# crown-E.net
KiCad netlist of a schematic drawn in EAGLE
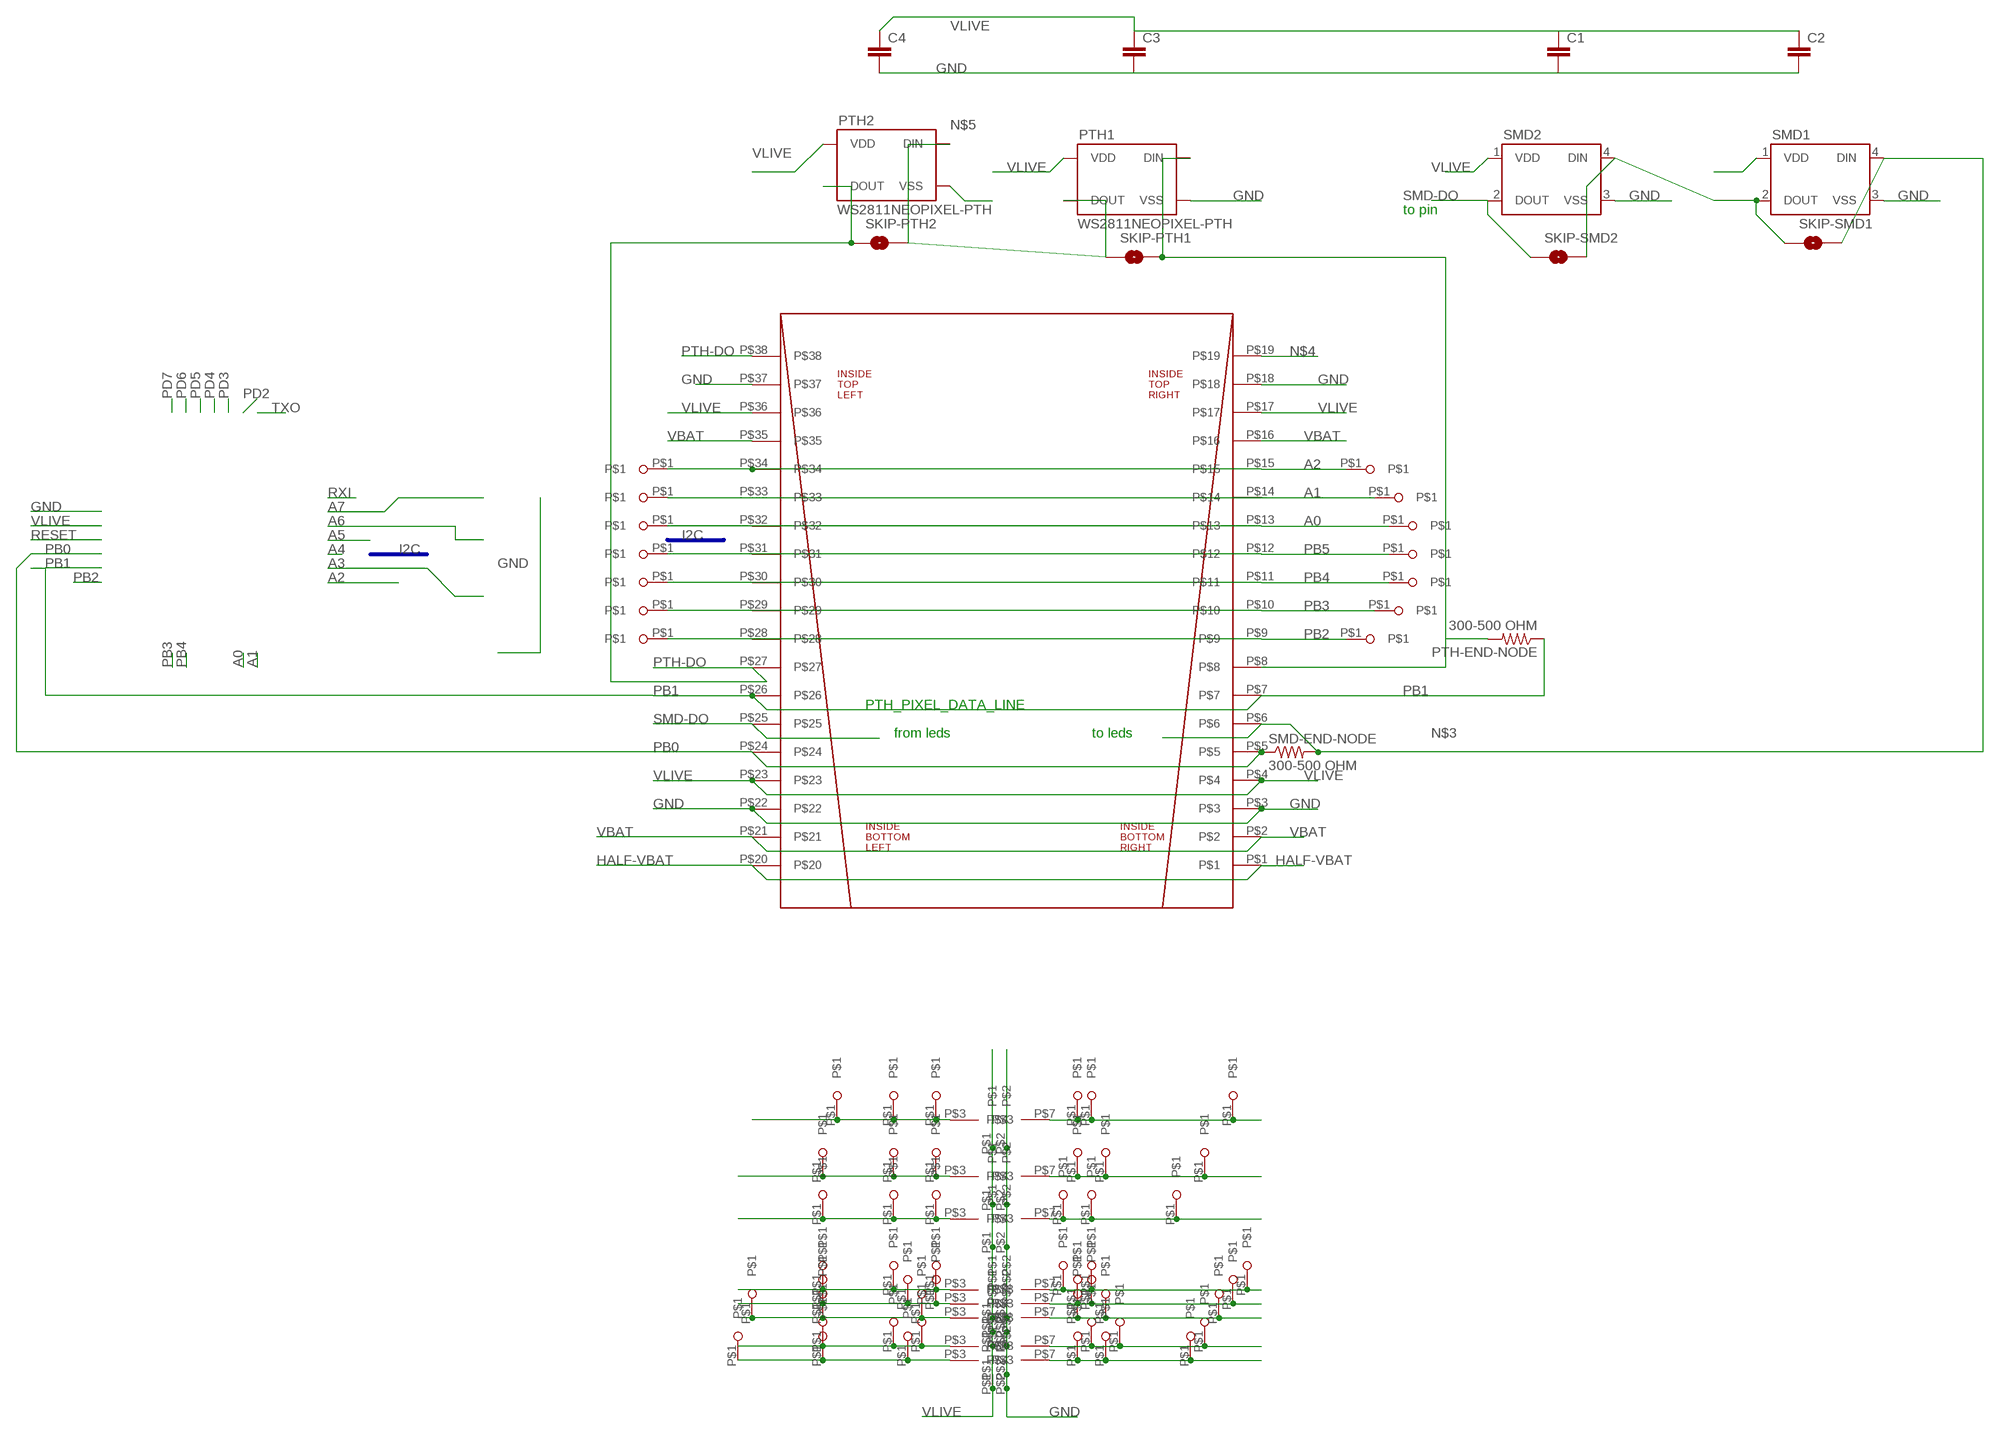
[diagram p0: schematic, sheet 1]

(export (version "E")
  (design (tool "Eeschema 10.0.6"))
  (components
    (comp (ref "C1")
      (value "CAP0805")
      (footprint "eagle-import:0805")
      (libsource (lib "eagle-import") (part "CAP0805"))
    )
    (comp (ref "C2")
      (value "CAP0805")
      (footprint "eagle-import:0805")
      (libsource (lib "eagle-import") (part "CAP0805"))
    )
    (comp (ref "C3")
      (value "CAP0805")
      (footprint "eagle-import:0805")
      (libsource (lib "eagle-import") (part "CAP0805"))
    )
    (comp (ref "C4")
      (value "CAP0805")
      (footprint "eagle-import:0805")
      (libsource (lib "eagle-import") (part "CAP0805"))
    )
    (comp (ref "PTH-END-NODE")
      (value "300-500 OHM")
      (footprint "eagle-import:0805")
      (libsource (lib "eagle-import") (part "RESISTOR0805-RES"))
    )
    (comp (ref "PTH1")
      (value "WS2811NEOPIXEL-PTH")
      (footprint "eagle-import:WS2811-PTH-FLAT")
      (libsource (lib "eagle-import") (part "WS2811NEOPIXEL-PTH"))
    )
    (comp (ref "PTH2")
      (value "WS2811NEOPIXEL-PTH")
      (footprint "eagle-import:WS2811-PTH-FLAT")
      (libsource (lib "eagle-import") (part "WS2811NEOPIXEL-PTH"))
    )
    (comp (ref "SKIP-PTH1")
      (value "SOLDERJUMPERNC2")
      (footprint "eagle-import:SJ_2S-NOTRACE")
      (libsource (lib "eagle-import") (part "SOLDERJUMPERNC2"))
    )
    (comp (ref "SKIP-PTH2")
      (value "SOLDERJUMPERNC2")
      (footprint "eagle-import:SJ_2S-NOTRACE")
      (libsource (lib "eagle-import") (part "SOLDERJUMPERNC2"))
    )
    (comp (ref "SKIP-SMD1")
      (value "SOLDERJUMPERNC2")
      (footprint "eagle-import:SJ_2S-NOTRACE")
      (libsource (lib "eagle-import") (part "SOLDERJUMPERNC2"))
    )
    (comp (ref "SKIP-SMD2")
      (value "SOLDERJUMPERNC2")
      (footprint "eagle-import:SJ_2S-NOTRACE")
      (libsource (lib "eagle-import") (part "SOLDERJUMPERNC2"))
    )
    (comp (ref "SMD-END-NODE")
      (value "300-500 OHM")
      (footprint "eagle-import:0805")
      (libsource (lib "eagle-import") (part "RESISTOR0805-RES"))
    )
    (comp (ref "SMD1")
      (value "WS2812B")
      (footprint "eagle-import:WS2812B")
      (libsource (lib "eagle-import") (part "WS2812B"))
    )
    (comp (ref "SMD2")
      (value "WS2812B")
      (footprint "eagle-import:WS2812B")
      (libsource (lib "eagle-import") (part "WS2812B"))
    )
    (comp (ref "U$1")
      (value "SMD_BREADBOARD")
      (footprint "eagle-import:SMD_BREADBOARD_4X")
      (libsource (lib "eagle-import") (part "SMD_BREADBOARD"))
    )
    (comp (ref "U$2")
      (value "CROWNSTANDARD")
      (footprint "eagle-import:CROWN")
      (libsource (lib "eagle-import") (part "CROWNSTANDARD"))
    )
    (comp (ref "U$3")
      (value "SMD_BREADBOARD")
      (footprint "eagle-import:SMD_BREADBOARD_4X")
      (libsource (lib "eagle-import") (part "SMD_BREADBOARD"))
    )
    (comp (ref "U$4")
      (value "SMD_BREADBOARD")
      (footprint "eagle-import:SMD_BREADBOARD_4X")
      (libsource (lib "eagle-import") (part "SMD_BREADBOARD"))
    )
    (comp (ref "U$5")
      (value "SMD_BREADBOARD")
      (footprint "eagle-import:SMD_BREADBOARD_4X")
      (libsource (lib "eagle-import") (part "SMD_BREADBOARD"))
    )
    (comp (ref "U$6")
      (value "SMD_BREADBOARD")
      (footprint "eagle-import:SMD_BREADBOARD_4X")
      (libsource (lib "eagle-import") (part "SMD_BREADBOARD"))
    )
    (comp (ref "U$7")
      (value "SMD_BREADBOARD")
      (footprint "eagle-import:SMD_BREADBOARD_4X")
      (libsource (lib "eagle-import") (part "SMD_BREADBOARD"))
    )
    (comp (ref "U$8")
      (value "SMD_BREADBOARD")
      (footprint "eagle-import:SMD_BREADBOARD_4X")
      (libsource (lib "eagle-import") (part "SMD_BREADBOARD"))
    )
    (comp (ref "U$9")
      (value "SMD_BREADBOARD")
      (footprint "eagle-import:SMD_BREADBOARD_4X")
      (libsource (lib "eagle-import") (part "SMD_BREADBOARD"))
    )
    (comp (ref "U$10")
      (value "SMD_PAD")
      (footprint "eagle-import:SMD_BREADBOARD_PAD")
      (libsource (lib "eagle-import") (part "SMD_PAD"))
    )
    (comp (ref "U$11")
      (value "SMD_PAD")
      (footprint "eagle-import:SMD_BREADBOARD_PAD")
      (libsource (lib "eagle-import") (part "SMD_PAD"))
    )
    (comp (ref "U$12")
      (value "SMD_PAD")
      (footprint "eagle-import:SMD_BREADBOARD_PAD")
      (libsource (lib "eagle-import") (part "SMD_PAD"))
    )
    (comp (ref "U$13")
      (value "SMD_PAD")
      (footprint "eagle-import:SMD_BREADBOARD_PAD")
      (libsource (lib "eagle-import") (part "SMD_PAD"))
    )
    (comp (ref "U$14")
      (value "SMD_PAD")
      (footprint "eagle-import:SMD_BREADBOARD_PAD")
      (libsource (lib "eagle-import") (part "SMD_PAD"))
    )
    (comp (ref "U$15")
      (value "SMD_PAD")
      (footprint "eagle-import:SMD_BREADBOARD_PAD")
      (libsource (lib "eagle-import") (part "SMD_PAD"))
    )
    (comp (ref "U$16")
      (value "SMD_PAD")
      (footprint "eagle-import:SMD_BREADBOARD_PAD")
      (libsource (lib "eagle-import") (part "SMD_PAD"))
    )
    (comp (ref "U$17")
      (value "SMD_PAD")
      (footprint "eagle-import:SMD_BREADBOARD_PAD")
      (libsource (lib "eagle-import") (part "SMD_PAD"))
    )
    (comp (ref "U$18")
      (value "SMD_PAD")
      (footprint "eagle-import:SMD_BREADBOARD_PAD")
      (libsource (lib "eagle-import") (part "SMD_PAD"))
    )
    (comp (ref "U$19")
      (value "SMD_PAD")
      (footprint "eagle-import:SMD_BREADBOARD_PAD")
      (libsource (lib "eagle-import") (part "SMD_PAD"))
    )
    (comp (ref "U$20")
      (value "SMD_PAD")
      (footprint "eagle-import:SMD_BREADBOARD_PAD")
      (libsource (lib "eagle-import") (part "SMD_PAD"))
    )
    (comp (ref "U$21")
      (value "SMD_PAD")
      (footprint "eagle-import:SMD_BREADBOARD_PAD")
      (libsource (lib "eagle-import") (part "SMD_PAD"))
    )
    (comp (ref "U$22")
      (value "SMD_PAD")
      (footprint "eagle-import:SMD_BREADBOARD_PAD")
      (libsource (lib "eagle-import") (part "SMD_PAD"))
    )
    (comp (ref "U$23")
      (value "SMD_PAD")
      (footprint "eagle-import:SMD_BREADBOARD_PAD")
      (libsource (lib "eagle-import") (part "SMD_PAD"))
    )
    (comp (ref "U$24")
      (value "SMD_PAD")
      (footprint "eagle-import:SMD_BREADBOARD_PAD")
      (libsource (lib "eagle-import") (part "SMD_PAD"))
    )
    (comp (ref "U$25")
      (value "SMD_PAD")
      (footprint "eagle-import:SMD_BREADBOARD_PAD")
      (libsource (lib "eagle-import") (part "SMD_PAD"))
    )
    (comp (ref "U$26")
      (value "SMD_PAD")
      (footprint "eagle-import:SMD_BREADBOARD_PAD")
      (libsource (lib "eagle-import") (part "SMD_PAD"))
    )
    (comp (ref "U$27")
      (value "SMD_PAD")
      (footprint "eagle-import:SMD_BREADBOARD_PAD")
      (libsource (lib "eagle-import") (part "SMD_PAD"))
    )
    (comp (ref "U$28")
      (value "SMD_PAD")
      (footprint "eagle-import:SMD_BREADBOARD_PAD")
      (libsource (lib "eagle-import") (part "SMD_PAD"))
    )
    (comp (ref "U$29")
      (value "SMD_PAD")
      (footprint "eagle-import:SMD_BREADBOARD_PAD")
      (libsource (lib "eagle-import") (part "SMD_PAD"))
    )
    (comp (ref "U$30")
      (value "SMD_PAD")
      (footprint "eagle-import:SMD_BREADBOARD_PAD")
      (libsource (lib "eagle-import") (part "SMD_PAD"))
    )
    (comp (ref "U$31")
      (value "SMD_PAD")
      (footprint "eagle-import:SMD_BREADBOARD_PAD")
      (libsource (lib "eagle-import") (part "SMD_PAD"))
    )
    (comp (ref "U$32")
      (value "SMD_PAD")
      (footprint "eagle-import:SMD_BREADBOARD_PAD")
      (libsource (lib "eagle-import") (part "SMD_PAD"))
    )
    (comp (ref "U$33")
      (value "SMD_PAD")
      (footprint "eagle-import:SMD_BREADBOARD_PAD")
      (libsource (lib "eagle-import") (part "SMD_PAD"))
    )
    (comp (ref "U$34")
      (value "SMD_PAD")
      (footprint "eagle-import:SMD_BREADBOARD_PAD")
      (libsource (lib "eagle-import") (part "SMD_PAD"))
    )
    (comp (ref "U$35")
      (value "SMD_PAD")
      (footprint "eagle-import:SMD_BREADBOARD_PAD")
      (libsource (lib "eagle-import") (part "SMD_PAD"))
    )
    (comp (ref "U$36")
      (value "SMD_PAD")
      (footprint "eagle-import:SMD_BREADBOARD_PAD")
      (libsource (lib "eagle-import") (part "SMD_PAD"))
    )
    (comp (ref "U$37")
      (value "SMD_PAD")
      (footprint "eagle-import:SMD_BREADBOARD_PAD")
      (libsource (lib "eagle-import") (part "SMD_PAD"))
    )
    (comp (ref "U$38")
      (value "SMD_PAD")
      (footprint "eagle-import:SMD_BREADBOARD_PAD")
      (libsource (lib "eagle-import") (part "SMD_PAD"))
    )
    (comp (ref "U$39")
      (value "SMD_PAD")
      (footprint "eagle-import:SMD_BREADBOARD_PAD")
      (libsource (lib "eagle-import") (part "SMD_PAD"))
    )
    (comp (ref "U$40")
      (value "SMD_PAD")
      (footprint "eagle-import:SMD_BREADBOARD_PAD")
      (libsource (lib "eagle-import") (part "SMD_PAD"))
    )
    (comp (ref "U$41")
      (value "SMD_PAD")
      (footprint "eagle-import:SMD_BREADBOARD_PAD")
      (libsource (lib "eagle-import") (part "SMD_PAD"))
    )
    (comp (ref "U$42")
      (value "SMD_PAD")
      (footprint "eagle-import:SMD_BREADBOARD_PAD")
      (libsource (lib "eagle-import") (part "SMD_PAD"))
    )
    (comp (ref "U$43")
      (value "SMD_PAD")
      (footprint "eagle-import:SMD_BREADBOARD_PAD")
      (libsource (lib "eagle-import") (part "SMD_PAD"))
    )
    (comp (ref "U$44")
      (value "SMD_PAD")
      (footprint "eagle-import:SMD_BREADBOARD_PAD")
      (libsource (lib "eagle-import") (part "SMD_PAD"))
    )
    (comp (ref "U$45")
      (value "SMD_PAD")
      (footprint "eagle-import:SMD_BREADBOARD_PAD")
      (libsource (lib "eagle-import") (part "SMD_PAD"))
    )
    (comp (ref "U$46")
      (value "SMD_PAD")
      (footprint "eagle-import:SMD_BREADBOARD_PAD")
      (libsource (lib "eagle-import") (part "SMD_PAD"))
    )
    (comp (ref "U$47")
      (value "SMD_PAD")
      (footprint "eagle-import:SMD_BREADBOARD_PAD")
      (libsource (lib "eagle-import") (part "SMD_PAD"))
    )
    (comp (ref "U$48")
      (value "SMD_PAD")
      (footprint "eagle-import:SMD_BREADBOARD_PAD")
      (libsource (lib "eagle-import") (part "SMD_PAD"))
    )
    (comp (ref "U$49")
      (value "SMD_PAD")
      (footprint "eagle-import:SMD_BREADBOARD_PAD")
      (libsource (lib "eagle-import") (part "SMD_PAD"))
    )
    (comp (ref "U$50")
      (value "SMD_PAD")
      (footprint "eagle-import:SMD_BREADBOARD_PAD")
      (libsource (lib "eagle-import") (part "SMD_PAD"))
    )
    (comp (ref "U$51")
      (value "SMD_PAD")
      (footprint "eagle-import:SMD_BREADBOARD_PAD")
      (libsource (lib "eagle-import") (part "SMD_PAD"))
    )
    (comp (ref "U$52")
      (value "SMD_PAD")
      (footprint "eagle-import:SMD_BREADBOARD_PAD")
      (libsource (lib "eagle-import") (part "SMD_PAD"))
    )
    (comp (ref "U$53")
      (value "SMD_PAD")
      (footprint "eagle-import:SMD_BREADBOARD_PAD")
      (libsource (lib "eagle-import") (part "SMD_PAD"))
    )
    (comp (ref "U$54")
      (value "SMD_PAD")
      (footprint "eagle-import:SMD_BREADBOARD_PAD")
      (libsource (lib "eagle-import") (part "SMD_PAD"))
    )
    (comp (ref "U$55")
      (value "SMD_PAD")
      (footprint "eagle-import:SMD_BREADBOARD_PAD")
      (libsource (lib "eagle-import") (part "SMD_PAD"))
    )
    (comp (ref "U$56")
      (value "SMD_PAD")
      (footprint "eagle-import:SMD_BREADBOARD_PAD")
      (libsource (lib "eagle-import") (part "SMD_PAD"))
    )
    (comp (ref "U$57")
      (value "SMD_PAD")
      (footprint "eagle-import:SMD_BREADBOARD_PAD")
      (libsource (lib "eagle-import") (part "SMD_PAD"))
    )
    (comp (ref "U$58")
      (value "SMD_PAD")
      (footprint "eagle-import:SMD_BREADBOARD_PAD")
      (libsource (lib "eagle-import") (part "SMD_PAD"))
    )
    (comp (ref "U$59")
      (value "SMD_PAD")
      (footprint "eagle-import:SMD_BREADBOARD_PAD")
      (libsource (lib "eagle-import") (part "SMD_PAD"))
    )
    (comp (ref "U$60")
      (value "SMD_PAD")
      (footprint "eagle-import:SMD_BREADBOARD_PAD")
      (libsource (lib "eagle-import") (part "SMD_PAD"))
    )
    (comp (ref "U$61")
      (value "SMD_PAD")
      (footprint "eagle-import:SMD_BREADBOARD_PAD")
      (libsource (lib "eagle-import") (part "SMD_PAD"))
    )
    (comp (ref "U$62")
      (value "SMD_PAD")
      (footprint "eagle-import:SMD_BREADBOARD_PAD")
      (libsource (lib "eagle-import") (part "SMD_PAD"))
    )
    (comp (ref "U$63")
      (value "SMD_PAD")
      (footprint "eagle-import:SMD_BREADBOARD_PAD")
      (libsource (lib "eagle-import") (part "SMD_PAD"))
    )
    (comp (ref "U$64")
      (value "SMD_PAD")
      (footprint "eagle-import:SMD_BREADBOARD_PAD")
      (libsource (lib "eagle-import") (part "SMD_PAD"))
    )
    (comp (ref "U$65")
      (value "SMD_PAD")
      (footprint "eagle-import:SMD_BREADBOARD_PAD")
      (libsource (lib "eagle-import") (part "SMD_PAD"))
    )
    (comp (ref "U$66")
      (value "SMD_PAD")
      (footprint "eagle-import:SMD_BREADBOARD_PAD")
      (libsource (lib "eagle-import") (part "SMD_PAD"))
    )
    (comp (ref "U$67")
      (value "SMD_PAD")
      (footprint "eagle-import:SMD_BREADBOARD_PAD")
      (libsource (lib "eagle-import") (part "SMD_PAD"))
    )
    (comp (ref "U$68")
      (value "SMD_PAD")
      (footprint "eagle-import:SMD_BREADBOARD_PAD")
      (libsource (lib "eagle-import") (part "SMD_PAD"))
    )
    (comp (ref "U$69")
      (value "SMD_PAD")
      (footprint "eagle-import:SMD_BREADBOARD_PAD")
      (libsource (lib "eagle-import") (part "SMD_PAD"))
    )
    (comp (ref "U$70")
      (value "SMD_PAD")
      (footprint "eagle-import:SMD_BREADBOARD_PAD")
      (libsource (lib "eagle-import") (part "SMD_PAD"))
    )
    (comp (ref "U$71")
      (value "SMD_PAD")
      (footprint "eagle-import:SMD_BREADBOARD_PAD")
      (libsource (lib "eagle-import") (part "SMD_PAD"))
    )
  )
  (nets
    (net (code "2") (name "/A0") (class "Default")
      (node (ref "U$2") (pin "P$13") (pinfunction "P$13_P$13") (pintype "bidirectional"))
      (node (ref "U$2") (pin "P$32") (pinfunction "P$32_P$32") (pintype "bidirectional"))
      (node (ref "U$44") (pin "P$1") (pinfunction "P$1_P$1") (pintype "bidirectional"))
      (node (ref "U$55") (pin "P$1") (pinfunction "P$1_P$1") (pintype "bidirectional"))
    )
    (net (code "3") (name "/A1") (class "Default")
      (node (ref "U$2") (pin "P$14") (pinfunction "P$14_P$14") (pintype "bidirectional"))
      (node (ref "U$2") (pin "P$33") (pinfunction "P$33_P$33") (pintype "bidirectional"))
      (node (ref "U$43") (pin "P$1") (pinfunction "P$1_P$1") (pintype "bidirectional"))
      (node (ref "U$56") (pin "P$1") (pinfunction "P$1_P$1") (pintype "bidirectional"))
    )
    (net (code "4") (name "/A2") (class "Default")
      (node (ref "U$2") (pin "P$15") (pinfunction "P$15_P$15") (pintype "bidirectional"))
      (node (ref "U$2") (pin "P$34") (pinfunction "P$34_P$34") (pintype "bidirectional"))
      (node (ref "U$42") (pin "P$1") (pinfunction "P$1_P$1") (pintype "bidirectional"))
      (node (ref "U$58") (pin "P$1") (pinfunction "P$1_P$1") (pintype "bidirectional"))
    )
    (net (code "10") (name "/GND") (class "Default")
      (node (ref "C1") (pin "2") (pinfunction "2_2") (pintype "passive"))
      (node (ref "C2") (pin "2") (pinfunction "2_2") (pintype "passive"))
      (node (ref "C3") (pin "2") (pinfunction "2_2") (pintype "passive"))
      (node (ref "C4") (pin "2") (pinfunction "2_2") (pintype "passive"))
      (node (ref "PTH1") (pin "P$2") (pinfunction "VSS_P$2") (pintype "power_in"))
      (node (ref "PTH1") (pin "P$6") (pinfunction "VSS_P$6") (pintype "power_in"))
      (node (ref "PTH2") (pin "P$2") (pinfunction "VSS_P$2") (pintype "power_in"))
      (node (ref "PTH2") (pin "P$6") (pinfunction "VSS_P$6") (pintype "power_in"))
      (node (ref "SMD1") (pin "3") (pinfunction "VSS_3") (pintype "power_in"))
      (node (ref "SMD2") (pin "3") (pinfunction "VSS_3") (pintype "power_in"))
      (node (ref "U$1") (pin "P$2") (pinfunction "P$2_P$2") (pintype "bidirectional"))
      (node (ref "U$2") (pin "P$18") (pinfunction "P$18_P$18") (pintype "bidirectional"))
      (node (ref "U$2") (pin "P$22") (pinfunction "P$22_P$22") (pintype "bidirectional"))
      (node (ref "U$2") (pin "P$3") (pinfunction "P$3_P$3") (pintype "bidirectional"))
      (node (ref "U$2") (pin "P$37") (pinfunction "P$37_P$37") (pintype "bidirectional"))
      (node (ref "U$3") (pin "P$2") (pinfunction "P$2_P$2") (pintype "bidirectional"))
      (node (ref "U$4") (pin "P$2") (pinfunction "P$2_P$2") (pintype "bidirectional"))
      (node (ref "U$5") (pin "P$2") (pinfunction "P$2_P$2") (pintype "bidirectional"))
      (node (ref "U$6") (pin "P$2") (pinfunction "P$2_P$2") (pintype "bidirectional"))
      (node (ref "U$7") (pin "P$2") (pinfunction "P$2_P$2") (pintype "bidirectional"))
      (node (ref "U$8") (pin "P$2") (pinfunction "P$2_P$2") (pintype "bidirectional"))
      (node (ref "U$9") (pin "P$2") (pinfunction "P$2_P$2") (pintype "bidirectional"))
    )
    (net (code "11") (name "/HALF-VBAT") (class "Default")
      (node (ref "U$2") (pin "P$1") (pinfunction "P$1_P$1") (pintype "bidirectional"))
      (node (ref "U$2") (pin "P$20") (pinfunction "P$20_P$20") (pintype "bidirectional"))
    )
    (net (code "12") (name "/N$3") (class "Default")
      (node (ref "SKIP-SMD1") (pin "2") (pinfunction "2_2") (pintype "passive"))
      (node (ref "SMD-END-NODE") (pin "2") (pinfunction "2_2") (pintype "passive"))
      (node (ref "SMD1") (pin "4") (pinfunction "DIN_4") (pintype "input"))
      (node (ref "U$2") (pin "P$6") (pinfunction "P$6_P$6") (pintype "bidirectional"))
    )
    (net (code "13") (name "/N$4") (class "Default")
      (node (ref "PTH-END-NODE") (pin "2") (pinfunction "2_2") (pintype "passive"))
      (node (ref "PTH1") (pin "P$4") (pinfunction "DIN_P$4") (pintype "input"))
      (node (ref "PTH1") (pin "P$8") (pinfunction "DIN_P$8") (pintype "input"))
      (node (ref "SKIP-PTH1") (pin "2") (pinfunction "2_2") (pintype "passive"))
      (node (ref "U$2") (pin "P$19") (pinfunction "P$19_P$19") (pintype "bidirectional"))
      (node (ref "U$2") (pin "P$8") (pinfunction "P$8_P$8") (pintype "bidirectional"))
    )
    (net (code "14") (name "/N$5") (class "Default")
      (node (ref "PTH1") (pin "P$1") (pinfunction "DOUT_P$1") (pintype "output"))
      (node (ref "PTH1") (pin "P$5") (pinfunction "DOUT_P$5") (pintype "output"))
      (node (ref "PTH2") (pin "P$4") (pinfunction "DIN_P$4") (pintype "input"))
      (node (ref "PTH2") (pin "P$8") (pinfunction "DIN_P$8") (pintype "input"))
      (node (ref "SKIP-PTH1") (pin "1") (pinfunction "1_1") (pintype "passive"))
      (node (ref "SKIP-PTH2") (pin "2") (pinfunction "2_2") (pintype "passive"))
    )
    (net (code "15") (name "/PB0") (class "Default")
      (node (ref "SMD-END-NODE") (pin "1") (pinfunction "1_1") (pintype "passive"))
      (node (ref "U$2") (pin "P$24") (pinfunction "P$24_P$24") (pintype "bidirectional"))
      (node (ref "U$2") (pin "P$5") (pinfunction "P$5_P$5") (pintype "bidirectional"))
    )
    (net (code "16") (name "/PB1") (class "Default")
      (node (ref "PTH-END-NODE") (pin "1") (pinfunction "1_1") (pintype "passive"))
      (node (ref "U$2") (pin "P$26") (pinfunction "P$26_P$26") (pintype "bidirectional"))
      (node (ref "U$2") (pin "P$7") (pinfunction "P$7_P$7") (pintype "bidirectional"))
    )
    (net (code "17") (name "/PB2") (class "Default")
      (node (ref "U$2") (pin "P$28") (pinfunction "P$28_P$28") (pintype "bidirectional"))
      (node (ref "U$2") (pin "P$9") (pinfunction "P$9_P$9") (pintype "bidirectional"))
      (node (ref "U$48") (pin "P$1") (pinfunction "P$1_P$1") (pintype "bidirectional"))
      (node (ref "U$51") (pin "P$1") (pinfunction "P$1_P$1") (pintype "bidirectional"))
    )
    (net (code "18") (name "/PB3") (class "Default")
      (node (ref "U$2") (pin "P$10") (pinfunction "P$10_P$10") (pintype "bidirectional"))
      (node (ref "U$2") (pin "P$29") (pinfunction "P$29_P$29") (pintype "bidirectional"))
      (node (ref "U$47") (pin "P$1") (pinfunction "P$1_P$1") (pintype "bidirectional"))
      (node (ref "U$52") (pin "P$1") (pinfunction "P$1_P$1") (pintype "bidirectional"))
    )
    (net (code "19") (name "/PB4") (class "Default")
      (node (ref "U$2") (pin "P$11") (pinfunction "P$11_P$11") (pintype "bidirectional"))
      (node (ref "U$2") (pin "P$30") (pinfunction "P$30_P$30") (pintype "bidirectional"))
      (node (ref "U$46") (pin "P$1") (pinfunction "P$1_P$1") (pintype "bidirectional"))
      (node (ref "U$53") (pin "P$1") (pinfunction "P$1_P$1") (pintype "bidirectional"))
    )
    (net (code "20") (name "/PB5") (class "Default")
      (node (ref "U$2") (pin "P$12") (pinfunction "P$12_P$12") (pintype "bidirectional"))
      (node (ref "U$2") (pin "P$31") (pinfunction "P$31_P$31") (pintype "bidirectional"))
      (node (ref "U$45") (pin "P$1") (pinfunction "P$1_P$1") (pintype "bidirectional"))
      (node (ref "U$54") (pin "P$1") (pinfunction "P$1_P$1") (pintype "bidirectional"))
    )
    (net (code "27") (name "/PTH-DO") (class "Default")
      (node (ref "PTH2") (pin "P$1") (pinfunction "DOUT_P$1") (pintype "output"))
      (node (ref "PTH2") (pin "P$5") (pinfunction "DOUT_P$5") (pintype "output"))
      (node (ref "SKIP-PTH2") (pin "1") (pinfunction "1_1") (pintype "passive"))
      (node (ref "U$2") (pin "P$27") (pinfunction "P$27_P$27") (pintype "bidirectional"))
      (node (ref "U$2") (pin "P$38") (pinfunction "P$38_P$38") (pintype "bidirectional"))
    )
    (net (code "30") (name "/SMD-DO") (class "Default")
      (node (ref "SKIP-SMD2") (pin "1") (pinfunction "1_1") (pintype "passive"))
      (node (ref "SMD2") (pin "2") (pinfunction "DOUT_2") (pintype "output"))
      (node (ref "U$2") (pin "P$25") (pinfunction "P$25_P$25") (pintype "bidirectional"))
    )
    (net (code "32") (name "/VBAT") (class "Default")
      (node (ref "U$2") (pin "P$16") (pinfunction "P$16_P$16") (pintype "bidirectional"))
      (node (ref "U$2") (pin "P$2") (pinfunction "P$2_P$2") (pintype "bidirectional"))
      (node (ref "U$2") (pin "P$21") (pinfunction "P$21_P$21") (pintype "bidirectional"))
      (node (ref "U$2") (pin "P$35") (pinfunction "P$35_P$35") (pintype "bidirectional"))
    )
    (net (code "33") (name "/VLIVE") (class "Default")
      (node (ref "C1") (pin "1") (pinfunction "1_1") (pintype "passive"))
      (node (ref "C2") (pin "1") (pinfunction "1_1") (pintype "passive"))
      (node (ref "C3") (pin "1") (pinfunction "1_1") (pintype "passive"))
      (node (ref "C4") (pin "1") (pinfunction "1_1") (pintype "passive"))
      (node (ref "PTH1") (pin "P$3") (pinfunction "VDD_P$3") (pintype "power_in"))
      (node (ref "PTH1") (pin "P$7") (pinfunction "VDD_P$7") (pintype "power_in"))
      (node (ref "PTH2") (pin "P$3") (pinfunction "VDD_P$3") (pintype "power_in"))
      (node (ref "PTH2") (pin "P$7") (pinfunction "VDD_P$7") (pintype "power_in"))
      (node (ref "SMD1") (pin "1") (pinfunction "VDD_1") (pintype "power_in"))
      (node (ref "SMD2") (pin "1") (pinfunction "VDD_1") (pintype "power_in"))
      (node (ref "U$1") (pin "P$1") (pinfunction "P$1_P$1") (pintype "bidirectional"))
      (node (ref "U$2") (pin "P$17") (pinfunction "P$17_P$17") (pintype "bidirectional"))
      (node (ref "U$2") (pin "P$23") (pinfunction "P$23_P$23") (pintype "bidirectional"))
      (node (ref "U$2") (pin "P$36") (pinfunction "P$36_P$36") (pintype "bidirectional"))
      (node (ref "U$2") (pin "P$4") (pinfunction "P$4_P$4") (pintype "bidirectional"))
      (node (ref "U$3") (pin "P$1") (pinfunction "P$1_P$1") (pintype "bidirectional"))
      (node (ref "U$4") (pin "P$1") (pinfunction "P$1_P$1") (pintype "bidirectional"))
      (node (ref "U$5") (pin "P$1") (pinfunction "P$1_P$1") (pintype "bidirectional"))
      (node (ref "U$6") (pin "P$1") (pinfunction "P$1_P$1") (pintype "bidirectional"))
      (node (ref "U$7") (pin "P$1") (pinfunction "P$1_P$1") (pintype "bidirectional"))
      (node (ref "U$8") (pin "P$1") (pinfunction "P$1_P$1") (pintype "bidirectional"))
      (node (ref "U$9") (pin "P$1") (pinfunction "P$1_P$1") (pintype "bidirectional"))
    )
    (net (code "35") (name "Net-(SMD1-DOUT)") (class "Default")
      (node (ref "SKIP-SMD1") (pin "1") (pinfunction "1_1") (pintype "passive"))
      (node (ref "SKIP-SMD2") (pin "2") (pinfunction "2_2") (pintype "passive"))
      (node (ref "SMD1") (pin "2") (pinfunction "DOUT_2") (pintype "output"))
      (node (ref "SMD2") (pin "4") (pinfunction "DIN_4") (pintype "input"))
    )
    (net (code "36") (name "Net-(U$1-P$4)") (class "Default")
      (node (ref "U$1") (pin "P$7") (pinfunction "P$4_P$7") (pintype "bidirectional"))
      (node (ref "U$26") (pin "P$1") (pinfunction "P$1_P$1") (pintype "bidirectional"))
      (node (ref "U$27") (pin "P$1") (pinfunction "P$1_P$1") (pintype "bidirectional"))
      (node (ref "U$64") (pin "P$1") (pinfunction "P$1_P$1") (pintype "bidirectional"))
    )
    (net (code "37") (name "Net-(U$1-PadP$3)") (class "Default")
      (node (ref "U$1") (pin "P$3") (pinfunction "P$3_P$3") (pintype "bidirectional"))
      (node (ref "U$24") (pin "P$1") (pinfunction "P$1_P$1") (pintype "bidirectional"))
      (node (ref "U$25") (pin "P$1") (pinfunction "P$1_P$1") (pintype "bidirectional"))
      (node (ref "U$63") (pin "P$1") (pinfunction "P$1_P$1") (pintype "bidirectional"))
    )
    (net (code "38") (name "Net-(U$3-P$4)") (class "Default")
      (node (ref "U$28") (pin "P$1") (pinfunction "P$1_P$1") (pintype "bidirectional"))
      (node (ref "U$29") (pin "P$1") (pinfunction "P$1_P$1") (pintype "bidirectional"))
      (node (ref "U$3") (pin "P$7") (pinfunction "P$4_P$7") (pintype "bidirectional"))
      (node (ref "U$65") (pin "P$1") (pinfunction "P$1_P$1") (pintype "bidirectional"))
    )
    (net (code "39") (name "Net-(U$4-P$4)") (class "Default")
      (node (ref "U$34") (pin "P$1") (pinfunction "P$1_P$1") (pintype "bidirectional"))
      (node (ref "U$35") (pin "P$1") (pinfunction "P$1_P$1") (pintype "bidirectional"))
      (node (ref "U$4") (pin "P$7") (pinfunction "P$4_P$7") (pintype "bidirectional"))
      (node (ref "U$68") (pin "P$1") (pinfunction "P$1_P$1") (pintype "bidirectional"))
    )
    (net (code "40") (name "Net-(U$5-P$4)") (class "Default")
      (node (ref "U$36") (pin "P$1") (pinfunction "P$1_P$1") (pintype "bidirectional"))
      (node (ref "U$37") (pin "P$1") (pinfunction "P$1_P$1") (pintype "bidirectional"))
      (node (ref "U$5") (pin "P$7") (pinfunction "P$4_P$7") (pintype "bidirectional"))
      (node (ref "U$69") (pin "P$1") (pinfunction "P$1_P$1") (pintype "bidirectional"))
    )
    (net (code "41") (name "Net-(U$6-P$4)") (class "Default")
      (node (ref "U$38") (pin "P$1") (pinfunction "P$1_P$1") (pintype "bidirectional"))
      (node (ref "U$39") (pin "P$1") (pinfunction "P$1_P$1") (pintype "bidirectional"))
      (node (ref "U$6") (pin "P$7") (pinfunction "P$4_P$7") (pintype "bidirectional"))
      (node (ref "U$70") (pin "P$1") (pinfunction "P$1_P$1") (pintype "bidirectional"))
    )
    (net (code "42") (name "Net-(U$7-P$4)") (class "Default")
      (node (ref "U$40") (pin "P$1") (pinfunction "P$1_P$1") (pintype "bidirectional"))
      (node (ref "U$41") (pin "P$1") (pinfunction "P$1_P$1") (pintype "bidirectional"))
      (node (ref "U$7") (pin "P$7") (pinfunction "P$4_P$7") (pintype "bidirectional"))
      (node (ref "U$71") (pin "P$1") (pinfunction "P$1_P$1") (pintype "bidirectional"))
    )
    (net (code "43") (name "Net-(U$8-P$4)") (class "Default")
      (node (ref "U$32") (pin "P$1") (pinfunction "P$1_P$1") (pintype "bidirectional"))
      (node (ref "U$33") (pin "P$1") (pinfunction "P$1_P$1") (pintype "bidirectional"))
      (node (ref "U$67") (pin "P$1") (pinfunction "P$1_P$1") (pintype "bidirectional"))
      (node (ref "U$8") (pin "P$7") (pinfunction "P$4_P$7") (pintype "bidirectional"))
    )
    (net (code "44") (name "Net-(U$9-P$4)") (class "Default")
      (node (ref "U$30") (pin "P$1") (pinfunction "P$1_P$1") (pintype "bidirectional"))
      (node (ref "U$31") (pin "P$1") (pinfunction "P$1_P$1") (pintype "bidirectional"))
      (node (ref "U$66") (pin "P$1") (pinfunction "P$1_P$1") (pintype "bidirectional"))
      (node (ref "U$9") (pin "P$7") (pinfunction "P$4_P$7") (pintype "bidirectional"))
    )
    (net (code "45") (name "Net-(U$10-PadP$1)") (class "Default")
      (node (ref "U$10") (pin "P$1") (pinfunction "P$1_P$1") (pintype "bidirectional"))
      (node (ref "U$11") (pin "P$1") (pinfunction "P$1_P$1") (pintype "bidirectional"))
      (node (ref "U$49") (pin "P$1") (pinfunction "P$1_P$1") (pintype "bidirectional"))
      (node (ref "U$7") (pin "P$3") (pinfunction "P$3_P$3") (pintype "bidirectional"))
    )
    (net (code "46") (name "Net-(U$12-PadP$1)") (class "Default")
      (node (ref "U$12") (pin "P$1") (pinfunction "P$1_P$1") (pintype "bidirectional"))
      (node (ref "U$13") (pin "P$1") (pinfunction "P$1_P$1") (pintype "bidirectional"))
      (node (ref "U$50") (pin "P$1") (pinfunction "P$1_P$1") (pintype "bidirectional"))
      (node (ref "U$6") (pin "P$3") (pinfunction "P$3_P$3") (pintype "bidirectional"))
    )
    (net (code "47") (name "Net-(U$14-PadP$1)") (class "Default")
      (node (ref "U$14") (pin "P$1") (pinfunction "P$1_P$1") (pintype "bidirectional"))
      (node (ref "U$15") (pin "P$1") (pinfunction "P$1_P$1") (pintype "bidirectional"))
      (node (ref "U$5") (pin "P$3") (pinfunction "P$3_P$3") (pintype "bidirectional"))
      (node (ref "U$57") (pin "P$1") (pinfunction "P$1_P$1") (pintype "bidirectional"))
    )
    (net (code "48") (name "Net-(U$16-PadP$1)") (class "Default")
      (node (ref "U$16") (pin "P$1") (pinfunction "P$1_P$1") (pintype "bidirectional"))
      (node (ref "U$17") (pin "P$1") (pinfunction "P$1_P$1") (pintype "bidirectional"))
      (node (ref "U$4") (pin "P$3") (pinfunction "P$3_P$3") (pintype "bidirectional"))
      (node (ref "U$59") (pin "P$1") (pinfunction "P$1_P$1") (pintype "bidirectional"))
    )
    (net (code "49") (name "Net-(U$18-PadP$1)") (class "Default")
      (node (ref "U$18") (pin "P$1") (pinfunction "P$1_P$1") (pintype "bidirectional"))
      (node (ref "U$19") (pin "P$1") (pinfunction "P$1_P$1") (pintype "bidirectional"))
      (node (ref "U$60") (pin "P$1") (pinfunction "P$1_P$1") (pintype "bidirectional"))
      (node (ref "U$8") (pin "P$3") (pinfunction "P$3_P$3") (pintype "bidirectional"))
    )
    (net (code "50") (name "Net-(U$20-PadP$1)") (class "Default")
      (node (ref "U$20") (pin "P$1") (pinfunction "P$1_P$1") (pintype "bidirectional"))
      (node (ref "U$21") (pin "P$1") (pinfunction "P$1_P$1") (pintype "bidirectional"))
      (node (ref "U$61") (pin "P$1") (pinfunction "P$1_P$1") (pintype "bidirectional"))
      (node (ref "U$9") (pin "P$3") (pinfunction "P$3_P$3") (pintype "bidirectional"))
    )
    (net (code "51") (name "Net-(U$22-PadP$1)") (class "Default")
      (node (ref "U$22") (pin "P$1") (pinfunction "P$1_P$1") (pintype "bidirectional"))
      (node (ref "U$23") (pin "P$1") (pinfunction "P$1_P$1") (pintype "bidirectional"))
      (node (ref "U$3") (pin "P$3") (pinfunction "P$3_P$3") (pintype "bidirectional"))
      (node (ref "U$62") (pin "P$1") (pinfunction "P$1_P$1") (pintype "bidirectional"))
    )
  )
)
